# SCH_ORANGE-FCU_2022-09-27.net
KiCad netlist of a schematic drawn in EasyEDA
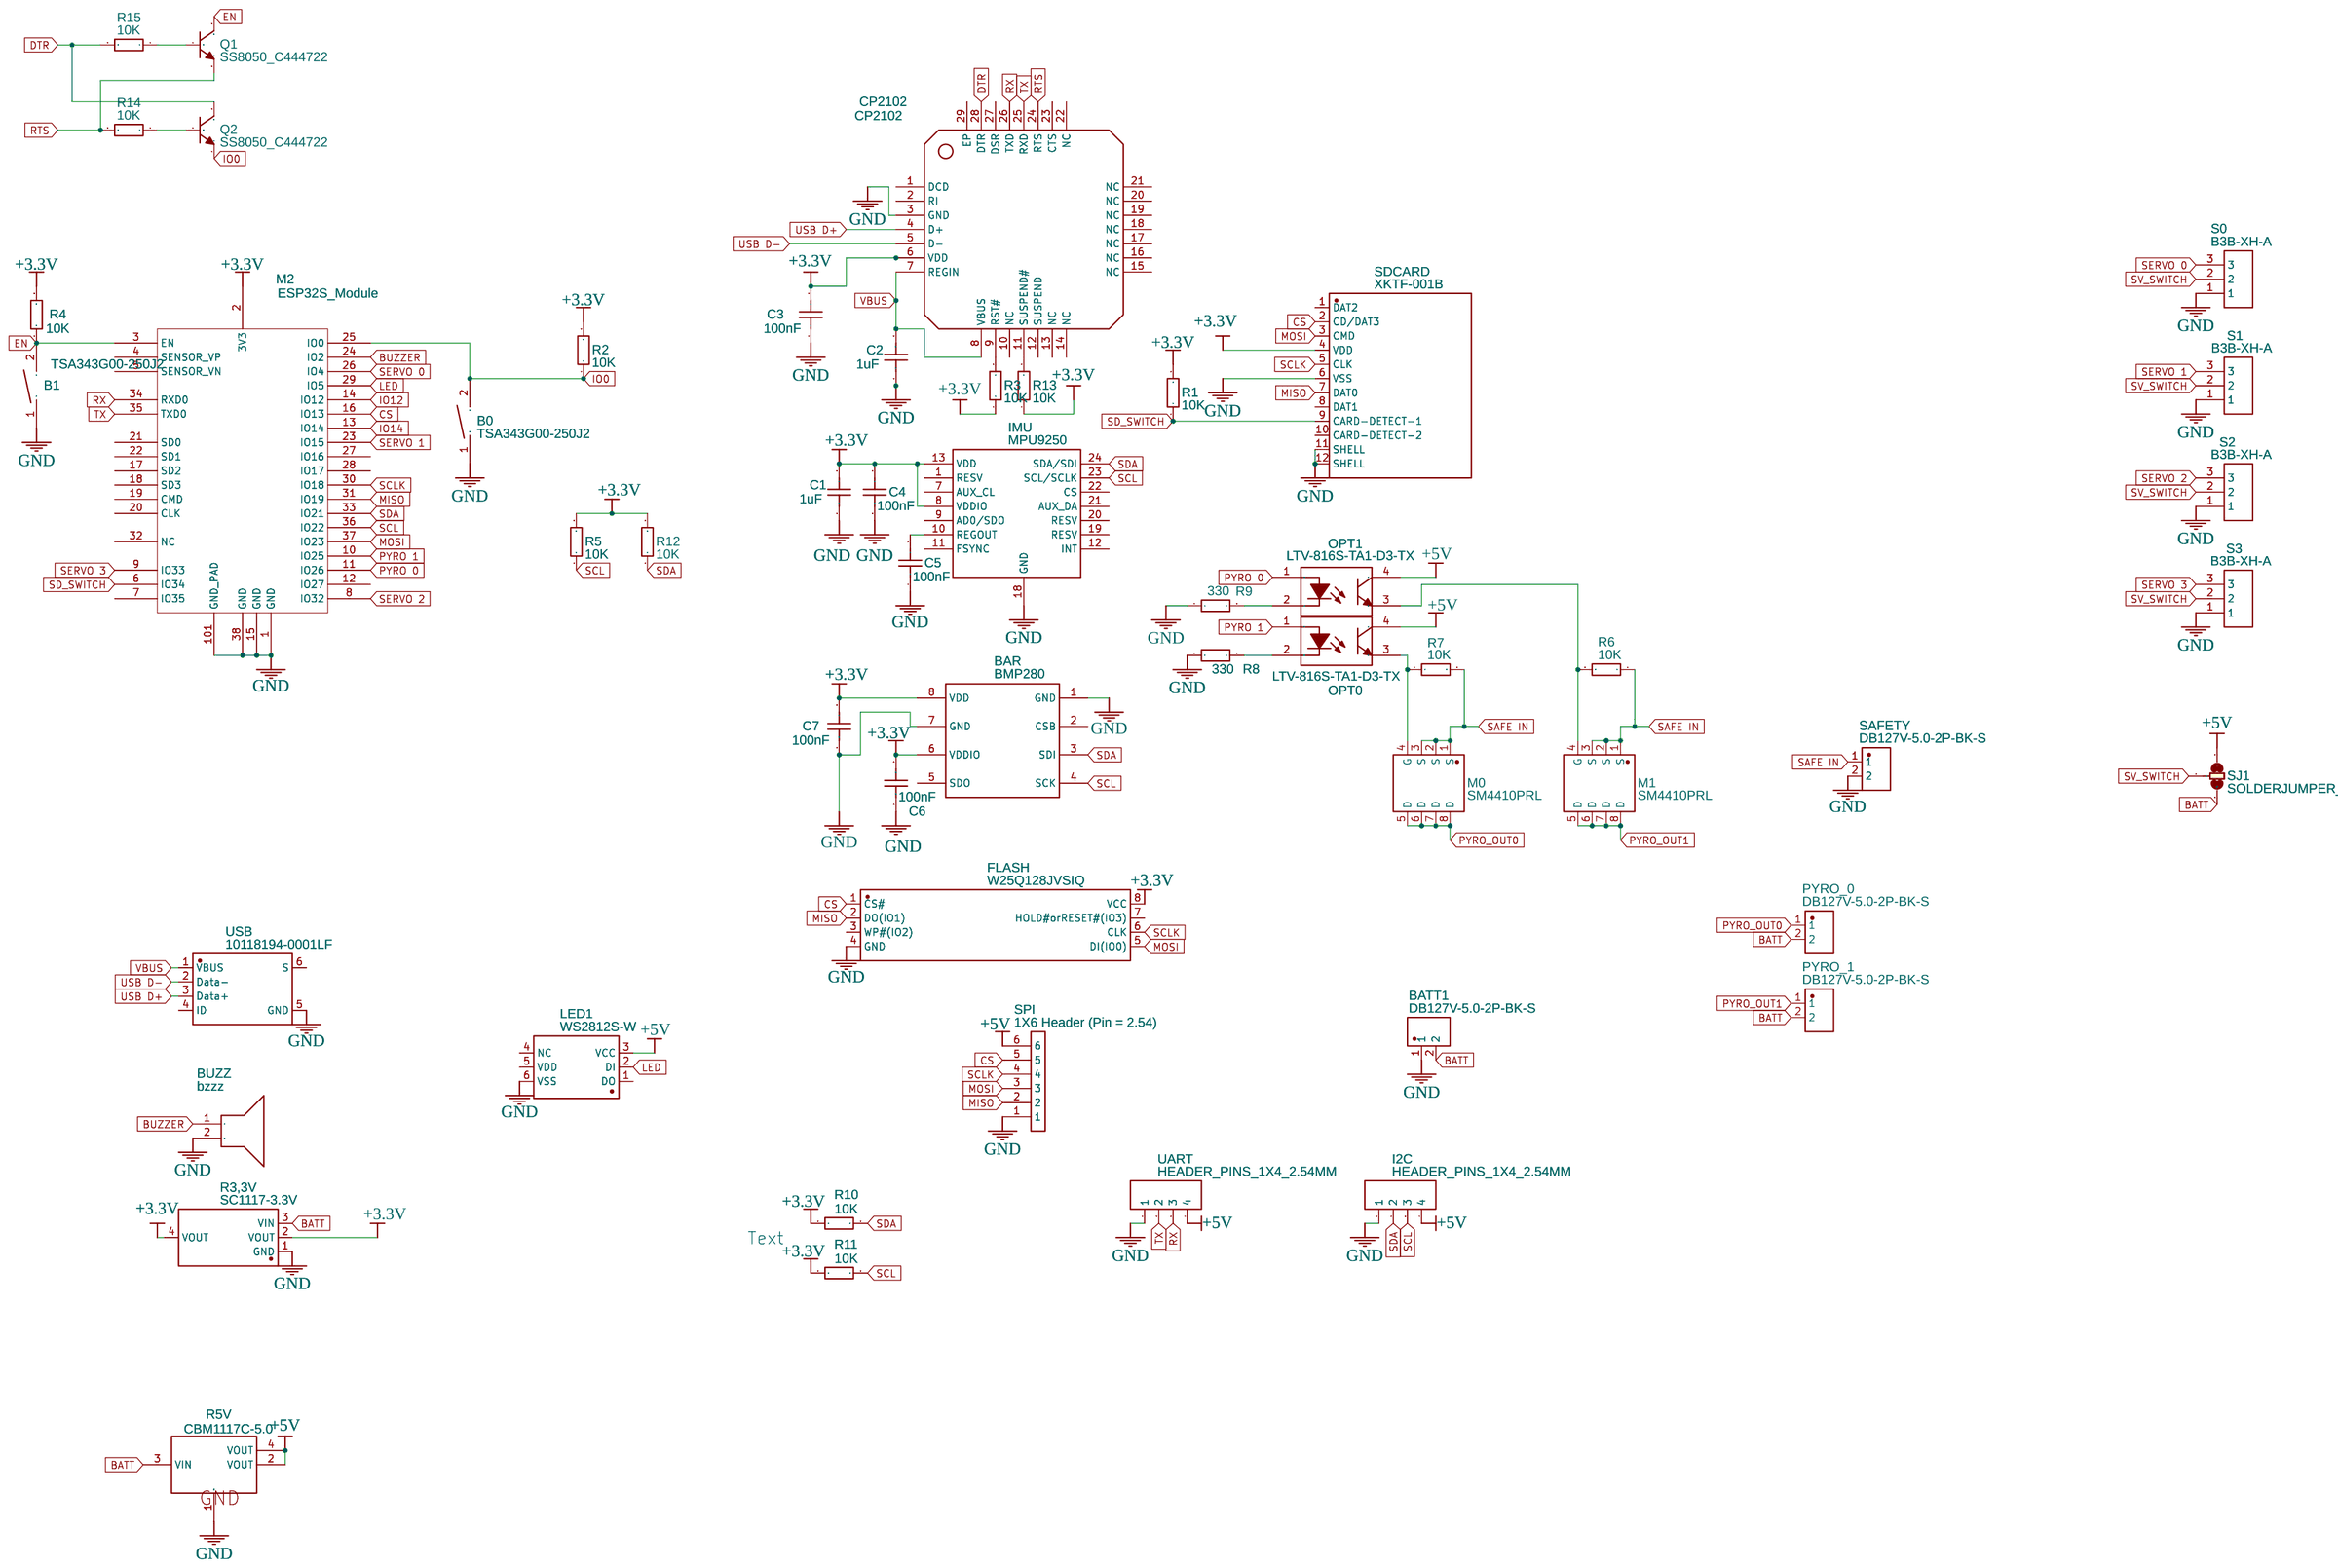
[diagram p0: schematic sheet]

(export (version "E")
  (design (tool "Eeschema 10.0.6"))
  (components
    (comp (ref "B0")
      (value "TSA343G00-250J2")
      (fields (field (name "BOM_Supplier Part") "C354946"))
      (libsource (lib "") (part "TSA343G00-250J2"))
    )
    (comp (ref "B1")
      (value "TSA343G00-250J2")
      (fields (field (name "BOM_Supplier Part") "C354946"))
      (libsource (lib "") (part "TSA343G00-250J2"))
    )
    (comp (ref "BAR")
      (value "BMP280")
      (fields (field (name "BOM_Supplier Part") "C83291"))
      (libsource (lib "") (part "BMP280"))
    )
    (comp (ref "BATT1")
      (value "DB127V-5.0-2P-BK-S")
      (fields (field (name "BOM_Supplier Part") "C430623"))
      (libsource (lib "") (part "DB127V-5.0-2P-BK-S_2"))
    )
    (comp (ref "BUZZ")
      (value "bzzz")
      (fields (field (name "BOM_Manufacturer Part") "FST-9018") (field (name "BOM_Supplier Part") "C391035"))
      (libsource (lib "") (part "FST-9018"))
    )
    (comp (ref "C1")
      (value "1uF")
      (fields
        (field (name "BOM_Manufacturer Part") "1206F105Z160CT")
        (field (name "BOM_Supplier Part") "C408911")
      )
      (libsource (lib "") (part "1206F105Z160CT"))
    )
    (comp (ref "C2")
      (value "1uF")
      (fields
        (field (name "BOM_Manufacturer Part") "1206F105Z160CT")
        (field (name "BOM_Supplier Part") "C408911")
      )
      (libsource (lib "") (part "1206F105Z160CT"))
    )
    (comp (ref "C3")
      (value "100nF")
      (fields
        (field (name "BOM_Manufacturer Part") "TCC1206X7R104K101DTS")
        (field (name "BOM_Supplier Part") "C696845")
      )
      (libsource (lib "") (part "TCC1206X7R104K101DTS"))
    )
    (comp (ref "C4")
      (value "100nF")
      (fields
        (field (name "BOM_Manufacturer Part") "TCC1206X7R104K101DTS")
        (field (name "BOM_Supplier Part") "C696845")
      )
      (libsource (lib "") (part "TCC1206X7R104K101DTS"))
    )
    (comp (ref "C5")
      (value "100nF")
      (fields
        (field (name "BOM_Manufacturer Part") "TCC1206X7R104K101DTS")
        (field (name "BOM_Supplier Part") "C696845")
      )
      (libsource (lib "") (part "TCC1206X7R104K101DTS"))
    )
    (comp (ref "C6")
      (value "100nF")
      (fields
        (field (name "BOM_Manufacturer Part") "TCC1206X7R104K101DTS")
        (field (name "BOM_Supplier Part") "C696845")
      )
      (libsource (lib "") (part "TCC1206X7R104K101DTS"))
    )
    (comp (ref "C7")
      (value "100nF")
      (fields
        (field (name "BOM_Manufacturer Part") "TCC1206X7R104K101DTS")
        (field (name "BOM_Supplier Part") "C696845")
      )
      (libsource (lib "") (part "TCC1206X7R104K101DTS"))
    )
    (comp (ref "CP2102")
      (value "CP2102")
      (fields (field (name "BOM_Manufacturer Part") "CP2102-GMR") (field (name "BOM_Supplier Part") "C6568"))
      (libsource (lib "") (part "CP2102-GMR"))
    )
    (comp (ref "FLASH")
      (value "W25Q128JVSIQ")
      (fields (field (name "BOM_Supplier Part") "C113767"))
      (libsource (lib "") (part "W25Q128JVSIQ"))
    )
    (comp (ref "I2C") (value "HEADER_PINS_1X4_2.54MM") (libsource (lib "") (part "HEADER_PINS_1X4_2.54MM")))
    (comp (ref "IMU") (value "MPU9250") (libsource (lib "") (part "MPU9250")))
    (comp (ref "LED1")
      (value "WS2812S-W")
      (fields (field (name "BOM_Supplier Part") "C114584"))
      (libsource (lib "") (part "WS2812S-W"))
    )
    (comp (ref "M0")
      (value "SM4410PRL")
      (fields (field (name "BOM_Supplier Part") "C235535"))
      (libsource (lib "") (part "SM4410PRL"))
    )
    (comp (ref "M1")
      (value "SM4410PRL")
      (fields (field (name "BOM_Supplier Part") "C235535"))
      (libsource (lib "") (part "SM4410PRL"))
    )
    (comp (ref "M2") (value "ESP32S_Module") (libsource (lib "") (part "ESP32S_Module")))
    (comp (ref "OPT0")
      (value "LTV-816S-TA1-D3-TX")
      (fields (field (name "BOM_Supplier Part") "C92647"))
      (libsource (lib "") (part "LTV-816S-TA1-D3-TX"))
    )
    (comp (ref "OPT1")
      (value "LTV-816S-TA1-D3-TX")
      (fields (field (name "BOM_Supplier Part") "C92647"))
      (libsource (lib "") (part "LTV-816S-TA1-D3-TX"))
    )
    (comp (ref "PYRO_0")
      (value "DB127V-5.0-2P-BK-S")
      (fields (field (name "BOM_Supplier Part") "C430623"))
      (libsource (lib "") (part "DB127V-5.0-2P-BK-S"))
    )
    (comp (ref "PYRO_1")
      (value "DB127V-5.0-2P-BK-S")
      (fields (field (name "BOM_Supplier Part") "C430623"))
      (libsource (lib "") (part "DB127V-5.0-2P-BK-S"))
    )
    (comp (ref "Q1")
      (value "SS8050_C444722")
      (fields (field (name "BOM_Manufacturer Part") "SS8050") (field (name "BOM_Supplier Part") "C444722"))
      (libsource (lib "") (part "SS8050_C444722"))
    )
    (comp (ref "Q2")
      (value "SS8050_C444722")
      (fields (field (name "BOM_Manufacturer Part") "SS8050") (field (name "BOM_Supplier Part") "C444722"))
      (libsource (lib "") (part "SS8050_C444722"))
    )
    (comp (ref "R1")
      (value "10K")
      (fields
        (field (name "BOM_Manufacturer Part") "AECR1206F10K0K9")
        (field (name "BOM_Supplier Part") "C328409")
      )
      (libsource (lib "") (part "AECR1206F10K0K9"))
    )
    (comp (ref "R2")
      (value "10K")
      (fields
        (field (name "BOM_Manufacturer Part") "AECR1206F10K0K9")
        (field (name "BOM_Supplier Part") "C328409")
      )
      (libsource (lib "") (part "AECR1206F10K0K9"))
    )
    (comp (ref "R3")
      (value "10K")
      (fields
        (field (name "BOM_Manufacturer Part") "AECR1206F10K0K9")
        (field (name "BOM_Supplier Part") "C328409")
      )
      (libsource (lib "") (part "AECR1206F10K0K9"))
    )
    (comp (ref "R3,3V")
      (value "SC1117-3.3V")
      (fields (field (name "BOM_Supplier Part") "C173386"))
      (libsource (lib "") (part "SC1117-3.3V"))
    )
    (comp (ref "R4")
      (value "10K")
      (fields
        (field (name "BOM_Manufacturer Part") "AECR1206F10K0K9")
        (field (name "BOM_Supplier Part") "C328409")
      )
      (libsource (lib "") (part "AECR1206F10K0K9"))
    )
    (comp (ref "R5")
      (value "10K")
      (fields
        (field (name "BOM_Manufacturer Part") "AECR1206F10K0K9")
        (field (name "BOM_Supplier Part") "C328409")
      )
      (libsource (lib "") (part "AECR1206F10K0K9"))
    )
    (comp (ref "R5V")
      (value "CBM1117C-5.0")
      (fields (field (name "BOM_Supplier Part") "C918918"))
      (libsource (lib "") (part "CBM1117C-5.0"))
    )
    (comp (ref "R6")
      (value "10K")
      (fields
        (field (name "BOM_Manufacturer Part") "AECR1206F10K0K9")
        (field (name "BOM_Supplier Part") "C328409")
      )
      (libsource (lib "") (part "AECR1206F10K0K9_2"))
    )
    (comp (ref "R7")
      (value "10K")
      (fields
        (field (name "BOM_Manufacturer Part") "AECR1206F10K0K9")
        (field (name "BOM_Supplier Part") "C328409")
      )
      (libsource (lib "") (part "AECR1206F10K0K9_1"))
    )
    (comp (ref "R8")
      (value "330")
      (fields
        (field (name "BOM_Manufacturer Part") "RTT06331JTP")
        (field (name "BOM_Supplier Part") "C104769")
      )
      (libsource (lib "") (part "RTT06331JTP"))
    )
    (comp (ref "R9")
      (value "330")
      (fields
        (field (name "BOM_Manufacturer Part") "RTT06331JTP")
        (field (name "BOM_Supplier Part") "C104769")
      )
      (libsource (lib "") (part "RTT06331JTP"))
    )
    (comp (ref "R10")
      (value "10K")
      (fields
        (field (name "BOM_Manufacturer Part") "AECR1206F10K0K9")
        (field (name "BOM_Supplier Part") "C328409")
      )
      (libsource (lib "") (part "AECR1206F10K0K9_1"))
    )
    (comp (ref "R11")
      (value "10K")
      (fields
        (field (name "BOM_Manufacturer Part") "AECR1206F10K0K9")
        (field (name "BOM_Supplier Part") "C328409")
      )
      (libsource (lib "") (part "AECR1206F10K0K9_1"))
    )
    (comp (ref "R12")
      (value "10K")
      (fields
        (field (name "BOM_Manufacturer Part") "AECR1206F10K0K9")
        (field (name "BOM_Supplier Part") "C328409")
      )
      (libsource (lib "") (part "AECR1206F10K0K9"))
    )
    (comp (ref "R13")
      (value "10K")
      (fields
        (field (name "BOM_Manufacturer Part") "AECR1206F10K0K9")
        (field (name "BOM_Supplier Part") "C328409")
      )
      (libsource (lib "") (part "AECR1206F10K0K9"))
    )
    (comp (ref "R14")
      (value "10K")
      (fields
        (field (name "BOM_Manufacturer Part") "AECR1206F10K0K9")
        (field (name "BOM_Supplier Part") "C328409")
      )
      (libsource (lib "") (part "AECR1206F10K0K9_2"))
    )
    (comp (ref "R15")
      (value "10K")
      (fields
        (field (name "BOM_Manufacturer Part") "AECR1206F10K0K9")
        (field (name "BOM_Supplier Part") "C328409")
      )
      (libsource (lib "") (part "AECR1206F10K0K9_2"))
    )
    (comp (ref "S0")
      (value "B3B-XH-A")
      (fields
        (field (name "BOM_Manufacturer Part") "B3B-XH-A(LF)(SN)")
        (field (name "BOM_Supplier Part") "C144394")
      )
      (libsource (lib "") (part "B3B-XH-A(LF)(SN)"))
    )
    (comp (ref "S1")
      (value "B3B-XH-A")
      (fields
        (field (name "BOM_Manufacturer Part") "B3B-XH-A(LF)(SN)")
        (field (name "BOM_Supplier Part") "C144394")
      )
      (libsource (lib "") (part "B3B-XH-A(LF)(SN)"))
    )
    (comp (ref "S2")
      (value "B3B-XH-A")
      (fields
        (field (name "BOM_Manufacturer Part") "B3B-XH-A(LF)(SN)")
        (field (name "BOM_Supplier Part") "C144394")
      )
      (libsource (lib "") (part "B3B-XH-A(LF)(SN)"))
    )
    (comp (ref "S3")
      (value "B3B-XH-A")
      (fields
        (field (name "BOM_Manufacturer Part") "B3B-XH-A(LF)(SN)")
        (field (name "BOM_Supplier Part") "C144394")
      )
      (libsource (lib "") (part "B3B-XH-A(LF)(SN)"))
    )
    (comp (ref "SAFETY")
      (value "DB127V-5.0-2P-BK-S")
      (fields (field (name "BOM_Supplier Part") "C430623"))
      (libsource (lib "") (part "DB127V-5.0-2P-BK-S_1"))
    )
    (comp (ref "SDCARD")
      (value "XKTF-001B")
      (fields (field (name "BOM_Supplier Part") "C381080"))
      (libsource (lib "") (part "XKTF-001B"))
    )
    (comp (ref "SJ1") (value "SOLDERJUMPER_2WAY-OLDS") (libsource (lib "") (part "SOLDERJUMPER_2WAY-OLDS")))
    (comp (ref "SPI")
      (value "1X6 Header (Pin = 2.54)")
      (fields (field (name "BOM_Manufacturer Part") "Male Header 2 pin"))
      (libsource (lib "") (part "1X6 Header (Pin = 2.54)"))
    )
    (comp (ref "UART")
      (value "HEADER_PINS_1X4_2.54MM")
      (libsource (lib "") (part "HEADER_PINS_1X4_2.54MM_1"))
    )
    (comp (ref "USB")
      (value "10118194-0001LF")
      (fields (field (name "BOM_Supplier Part") "C132563"))
      (libsource (lib "") (part "10118194-0001LF"))
    )
  )
  (nets
    (net (code "1") (name "+3.3V") (class "Default")
      (node (ref "BAR") (pin "6") (pinfunction "VDDIO_6") (pintype "unspecified"))
      (node (ref "BAR") (pin "8") (pinfunction "VDD_8") (pintype "unspecified"))
      (node (ref "C1") (pin "2") (pinfunction "2_2") (pintype "unspecified"))
      (node (ref "C3") (pin "2") (pinfunction "2_2") (pintype "unspecified"))
      (node (ref "C4") (pin "2") (pinfunction "2_2") (pintype "unspecified"))
      (node (ref "C6") (pin "2") (pinfunction "2_2") (pintype "unspecified"))
      (node (ref "C7") (pin "2") (pinfunction "2_2") (pintype "unspecified"))
      (node (ref "CP2102") (pin "6") (pinfunction "VDD_6") (pintype "unspecified"))
      (node (ref "FLASH") (pin "8") (pinfunction "VCC_8") (pintype "unspecified"))
      (node (ref "IMU") (pin "13") (pinfunction "VDD_13") (pintype "unspecified"))
      (node (ref "IMU") (pin "8") (pinfunction "VDDIO_8") (pintype "unspecified"))
      (node (ref "M2") (pin "2") (pinfunction "3V3_2") (pintype "passive"))
      (node (ref "R1") (pin "2") (pinfunction "2_2") (pintype "unspecified"))
      (node (ref "R10") (pin "1") (pinfunction "1_1") (pintype "unspecified"))
      (node (ref "R11") (pin "1") (pinfunction "1_1") (pintype "unspecified"))
      (node (ref "R12") (pin "2") (pinfunction "2_2") (pintype "unspecified"))
      (node (ref "R13") (pin "1") (pinfunction "1_1") (pintype "unspecified"))
      (node (ref "R2") (pin "2") (pinfunction "2_2") (pintype "unspecified"))
      (node (ref "R3") (pin "1") (pinfunction "1_1") (pintype "unspecified"))
      (node (ref "R3,3V") (pin "2") (pinfunction "VOUT_2") (pintype "unspecified"))
      (node (ref "R3,3V") (pin "4") (pinfunction "VOUT_4") (pintype "unspecified"))
      (node (ref "R4") (pin "2") (pinfunction "2_2") (pintype "unspecified"))
      (node (ref "R5") (pin "2") (pinfunction "2_2") (pintype "unspecified"))
      (node (ref "SDCARD") (pin "4") (pinfunction "VDD_4") (pintype "unspecified"))
    )
    (net (code "2") (name "+5V") (class "Default")
      (node (ref "I2C") (pin "4") (pinfunction "4_4") (pintype "unspecified"))
      (node (ref "LED1") (pin "3") (pinfunction "VCC_3") (pintype "unspecified"))
      (node (ref "OPT0") (pin "4") (pinfunction "4_4") (pintype "unspecified"))
      (node (ref "OPT1") (pin "4") (pinfunction "4_4") (pintype "unspecified"))
      (node (ref "R5V") (pin "2") (pinfunction "VOUT_2") (pintype "passive"))
      (node (ref "R5V") (pin "4") (pinfunction "VOUT_4") (pintype "passive"))
      (node (ref "SJ1") (pin "1") (pinfunction "1_1") (pintype "unspecified"))
      (node (ref "SPI") (pin "6") (pinfunction "6_6") (pintype "unspecified"))
      (node (ref "UART") (pin "4") (pinfunction "4_4") (pintype "unspecified"))
    )
    (net (code "3") (name "BATT") (class "Default")
      (node (ref "BATT1") (pin "2") (pinfunction "2_2") (pintype "unspecified"))
      (node (ref "PYRO_0") (pin "2") (pinfunction "2_2") (pintype "unspecified"))
      (node (ref "PYRO_1") (pin "2") (pinfunction "2_2") (pintype "unspecified"))
      (node (ref "R3,3V") (pin "3") (pinfunction "VIN_3") (pintype "unspecified"))
      (node (ref "R5V") (pin "3") (pinfunction "VIN_3") (pintype "passive"))
      (node (ref "SJ1") (pin "3") (pinfunction "3_3") (pintype "unspecified"))
    )
    (net (code "4") (name "BUZZER") (class "Default")
      (node (ref "BUZZ") (pin "1") (pinfunction "1_1") (pintype "unspecified"))
      (node (ref "M2") (pin "24") (pinfunction "IO2_24") (pintype "unspecified"))
    )
    (net (code "5") (name "CS") (class "Default")
      (node (ref "FLASH") (pin "1") (pinfunction "CS#_1") (pintype "unspecified"))
      (node (ref "M2") (pin "16") (pinfunction "IO13_16") (pintype "unspecified"))
      (node (ref "SDCARD") (pin "2") (pinfunction "CD/DAT3_2") (pintype "unspecified"))
      (node (ref "SPI") (pin "5") (pinfunction "5_5") (pintype "unspecified"))
    )
    (net (code "6") (name "DTR") (class "Default")
      (node (ref "CP2102") (pin "28") (pinfunction "DTR_28") (pintype "unspecified"))
      (node (ref "Q2") (pin "3") (pinfunction "C_3") (pintype "unspecified"))
      (node (ref "R15") (pin "2") (pinfunction "2_2") (pintype "unspecified"))
    )
    (net (code "7") (name "EN") (class "Default")
      (node (ref "B1") (pin "2") (pinfunction "2_2") (pintype "input"))
      (node (ref "M2") (pin "3") (pinfunction "EN_3") (pintype "passive"))
      (node (ref "Q1") (pin "3") (pinfunction "C_3") (pintype "unspecified"))
      (node (ref "R4") (pin "1") (pinfunction "1_1") (pintype "unspecified"))
    )
    (net (code "8") (name "GND") (class "Default")
      (node (ref "B0") (pin "1") (pinfunction "1_1") (pintype "input"))
      (node (ref "B1") (pin "1") (pinfunction "1_1") (pintype "input"))
      (node (ref "BAR") (pin "1") (pinfunction "GND_1") (pintype "unspecified"))
      (node (ref "BAR") (pin "7") (pinfunction "GND_7") (pintype "unspecified"))
      (node (ref "BATT1") (pin "1") (pinfunction "1_1") (pintype "unspecified"))
      (node (ref "BUZZ") (pin "2") (pinfunction "2_2") (pintype "unspecified"))
      (node (ref "C1") (pin "1") (pinfunction "1_1") (pintype "unspecified"))
      (node (ref "C2") (pin "1") (pinfunction "1_1") (pintype "unspecified"))
      (node (ref "C3") (pin "1") (pinfunction "1_1") (pintype "unspecified"))
      (node (ref "C4") (pin "1") (pinfunction "1_1") (pintype "unspecified"))
      (node (ref "C5") (pin "1") (pinfunction "1_1") (pintype "unspecified"))
      (node (ref "C6") (pin "1") (pinfunction "1_1") (pintype "unspecified"))
      (node (ref "C7") (pin "1") (pinfunction "1_1") (pintype "unspecified"))
      (node (ref "CP2102") (pin "3") (pinfunction "GND_3") (pintype "unspecified"))
      (node (ref "FLASH") (pin "4") (pinfunction "GND_4") (pintype "unspecified"))
      (node (ref "I2C") (pin "1") (pinfunction "1_1") (pintype "unspecified"))
      (node (ref "IMU") (pin "18") (pinfunction "GND_18") (pintype "unspecified"))
      (node (ref "LED1") (pin "6") (pinfunction "VSS_6") (pintype "unspecified"))
      (node (ref "M2") (pin "1") (pinfunction "GND_1") (pintype "passive"))
      (node (ref "M2") (pin "101") (pinfunction "GND_PAD_101") (pintype "passive"))
      (node (ref "M2") (pin "15") (pinfunction "GND_15") (pintype "passive"))
      (node (ref "M2") (pin "38") (pinfunction "GND_38") (pintype "passive"))
      (node (ref "R3,3V") (pin "1") (pinfunction "GND_1") (pintype "unspecified"))
      (node (ref "R5V") (pin "1") (pinfunction "GND_1") (pintype "passive"))
      (node (ref "R8") (pin "1") (pinfunction "1_1") (pintype "input"))
      (node (ref "R9") (pin "1") (pinfunction "1_1") (pintype "input"))
      (node (ref "S0") (pin "1") (pinfunction "1_1") (pintype "unspecified"))
      (node (ref "S1") (pin "1") (pinfunction "1_1") (pintype "unspecified"))
      (node (ref "S2") (pin "1") (pinfunction "1_1") (pintype "unspecified"))
      (node (ref "S3") (pin "1") (pinfunction "1_1") (pintype "unspecified"))
      (node (ref "SAFETY") (pin "2") (pinfunction "2_2") (pintype "unspecified"))
      (node (ref "SDCARD") (pin "11") (pinfunction "SHELL_11") (pintype "unspecified"))
      (node (ref "SDCARD") (pin "12") (pinfunction "SHELL_12") (pintype "unspecified"))
      (node (ref "SDCARD") (pin "6") (pinfunction "VSS_6") (pintype "unspecified"))
      (node (ref "SPI") (pin "1") (pinfunction "1_1") (pintype "unspecified"))
      (node (ref "UART") (pin "1") (pinfunction "1_1") (pintype "unspecified"))
      (node (ref "USB") (pin "5") (pinfunction "GND_5") (pintype "unspecified"))
    )
    (net (code "9") (name "IO0") (class "Default")
      (node (ref "B0") (pin "2") (pinfunction "2_2") (pintype "input"))
      (node (ref "M2") (pin "25") (pinfunction "IO0_25") (pintype "unspecified"))
      (node (ref "Q2") (pin "2") (pinfunction "E_2") (pintype "unspecified"))
      (node (ref "R2") (pin "1") (pinfunction "1_1") (pintype "unspecified"))
    )
    (net (code "10") (name "IO12") (class "Default")
      (node (ref "M2") (pin "14") (pinfunction "IO12_14") (pintype "unspecified"))
    )
    (net (code "11") (name "IO14") (class "Default")
      (node (ref "M2") (pin "13") (pinfunction "IO14_13") (pintype "unspecified"))
    )
    (net (code "12") (name "LED") (class "Default")
      (node (ref "LED1") (pin "2") (pinfunction "DI_2") (pintype "unspecified"))
      (node (ref "M2") (pin "29") (pinfunction "IO5_29") (pintype "unspecified"))
    )
    (net (code "13") (name "MISO") (class "Default")
      (node (ref "FLASH") (pin "2") (pinfunction "DO(IO1)_2") (pintype "unspecified"))
      (node (ref "M2") (pin "31") (pinfunction "IO19_31") (pintype "unspecified"))
      (node (ref "SDCARD") (pin "7") (pinfunction "DAT0_7") (pintype "unspecified"))
      (node (ref "SPI") (pin "2") (pinfunction "2_2") (pintype "unspecified"))
    )
    (net (code "14") (name "MOSI") (class "Default")
      (node (ref "FLASH") (pin "5") (pinfunction "DI(IO0)_5") (pintype "unspecified"))
      (node (ref "M2") (pin "37") (pinfunction "IO23_37") (pintype "unspecified"))
      (node (ref "SDCARD") (pin "3") (pinfunction "CMD_3") (pintype "unspecified"))
      (node (ref "SPI") (pin "3") (pinfunction "3_3") (pintype "unspecified"))
    )
    (net (code "15") (name "Net-(CP2102-RST#)") (class "Default")
      (node (ref "CP2102") (pin "9") (pinfunction "RST#_9") (pintype "unspecified"))
      (node (ref "R3") (pin "2") (pinfunction "2_2") (pintype "unspecified"))
    )
    (net (code "16") (name "Net-(CP2102-SUSPEND#)") (class "Default")
      (node (ref "CP2102") (pin "11") (pinfunction "SUSPEND#_11") (pintype "unspecified"))
      (node (ref "R13") (pin "2") (pinfunction "2_2") (pintype "unspecified"))
    )
    (net (code "17") (name "Net-(IMU-REGOUT)") (class "Default")
      (node (ref "C5") (pin "2") (pinfunction "2_2") (pintype "unspecified"))
      (node (ref "IMU") (pin "10") (pinfunction "REGOUT_10") (pintype "unspecified"))
    )
    (net (code "18") (name "Net-(M0-G)") (class "Default")
      (node (ref "M0") (pin "4") (pinfunction "G_4") (pintype "unspecified"))
      (node (ref "OPT0") (pin "3") (pinfunction "3_3") (pintype "unspecified"))
      (node (ref "R7") (pin "1") (pinfunction "1_1") (pintype "unspecified"))
    )
    (net (code "19") (name "Net-(M1-G)") (class "Default")
      (node (ref "M1") (pin "4") (pinfunction "G_4") (pintype "unspecified"))
      (node (ref "OPT1") (pin "3") (pinfunction "3_3") (pintype "unspecified"))
      (node (ref "R6") (pin "2") (pinfunction "2_2") (pintype "unspecified"))
    )
    (net (code "20") (name "Net-(OPT0-Pad2)") (class "Default")
      (node (ref "OPT0") (pin "2") (pinfunction "2_2") (pintype "unspecified"))
      (node (ref "R8") (pin "2") (pinfunction "2_2") (pintype "input"))
    )
    (net (code "21") (name "Net-(OPT1-Pad2)") (class "Default")
      (node (ref "OPT1") (pin "2") (pinfunction "2_2") (pintype "unspecified"))
      (node (ref "R9") (pin "2") (pinfunction "2_2") (pintype "input"))
    )
    (net (code "22") (name "Net-(Q1-B)") (class "Default")
      (node (ref "Q1") (pin "1") (pinfunction "B_1") (pintype "unspecified"))
      (node (ref "R15") (pin "1") (pinfunction "1_1") (pintype "unspecified"))
    )
    (net (code "23") (name "Net-(Q2-B)") (class "Default")
      (node (ref "Q2") (pin "1") (pinfunction "B_1") (pintype "unspecified"))
      (node (ref "R14") (pin "1") (pinfunction "1_1") (pintype "unspecified"))
    )
    (net (code "24") (name "PYRO 0") (class "Default")
      (node (ref "M2") (pin "11") (pinfunction "IO26_11") (pintype "unspecified"))
      (node (ref "OPT1") (pin "1") (pinfunction "1_1") (pintype "unspecified"))
    )
    (net (code "25") (name "PYRO 1") (class "Default")
      (node (ref "M2") (pin "10") (pinfunction "IO25_10") (pintype "unspecified"))
      (node (ref "OPT0") (pin "1") (pinfunction "1_1") (pintype "unspecified"))
    )
    (net (code "26") (name "PYRO_OUT0") (class "Default")
      (node (ref "M0") (pin "5") (pinfunction "D_5") (pintype "unspecified"))
      (node (ref "M0") (pin "6") (pinfunction "D_6") (pintype "unspecified"))
      (node (ref "M0") (pin "7") (pinfunction "D_7") (pintype "unspecified"))
      (node (ref "M0") (pin "8") (pinfunction "D_8") (pintype "unspecified"))
      (node (ref "PYRO_0") (pin "1") (pinfunction "1_1") (pintype "unspecified"))
    )
    (net (code "27") (name "PYRO_OUT1") (class "Default")
      (node (ref "M1") (pin "5") (pinfunction "D_5") (pintype "unspecified"))
      (node (ref "M1") (pin "6") (pinfunction "D_6") (pintype "unspecified"))
      (node (ref "M1") (pin "7") (pinfunction "D_7") (pintype "unspecified"))
      (node (ref "M1") (pin "8") (pinfunction "D_8") (pintype "unspecified"))
      (node (ref "PYRO_1") (pin "1") (pinfunction "1_1") (pintype "unspecified"))
    )
    (net (code "28") (name "RTS") (class "Default")
      (node (ref "CP2102") (pin "24") (pinfunction "RTS_24") (pintype "unspecified"))
      (node (ref "Q1") (pin "2") (pinfunction "E_2") (pintype "unspecified"))
      (node (ref "R14") (pin "2") (pinfunction "2_2") (pintype "unspecified"))
    )
    (net (code "29") (name "RX") (class "Default")
      (node (ref "CP2102") (pin "26") (pinfunction "TXD_26") (pintype "unspecified"))
      (node (ref "M2") (pin "34") (pinfunction "RXD0_34") (pintype "unspecified"))
      (node (ref "UART") (pin "3") (pinfunction "3_3") (pintype "unspecified"))
    )
    (net (code "30") (name "SAFE IN") (class "Default")
      (node (ref "M0") (pin "1") (pinfunction "S_1") (pintype "unspecified"))
      (node (ref "M0") (pin "2") (pinfunction "S_2") (pintype "unspecified"))
      (node (ref "M0") (pin "3") (pinfunction "S_3") (pintype "unspecified"))
      (node (ref "M1") (pin "1") (pinfunction "S_1") (pintype "unspecified"))
      (node (ref "M1") (pin "2") (pinfunction "S_2") (pintype "unspecified"))
      (node (ref "M1") (pin "3") (pinfunction "S_3") (pintype "unspecified"))
      (node (ref "R6") (pin "1") (pinfunction "1_1") (pintype "unspecified"))
      (node (ref "R7") (pin "2") (pinfunction "2_2") (pintype "unspecified"))
      (node (ref "SAFETY") (pin "1") (pinfunction "1_1") (pintype "unspecified"))
    )
    (net (code "31") (name "SCL") (class "Default")
      (node (ref "BAR") (pin "4") (pinfunction "SCK_4") (pintype "unspecified"))
      (node (ref "I2C") (pin "3") (pinfunction "3_3") (pintype "unspecified"))
      (node (ref "IMU") (pin "23") (pinfunction "SCL/SCLK_23") (pintype "unspecified"))
      (node (ref "M2") (pin "36") (pinfunction "IO22_36") (pintype "unspecified"))
      (node (ref "R11") (pin "2") (pinfunction "2_2") (pintype "unspecified"))
      (node (ref "R5") (pin "1") (pinfunction "1_1") (pintype "unspecified"))
    )
    (net (code "32") (name "SCLK") (class "Default")
      (node (ref "FLASH") (pin "6") (pinfunction "CLK_6") (pintype "unspecified"))
      (node (ref "M2") (pin "30") (pinfunction "IO18_30") (pintype "unspecified"))
      (node (ref "SDCARD") (pin "5") (pinfunction "CLK_5") (pintype "unspecified"))
      (node (ref "SPI") (pin "4") (pinfunction "4_4") (pintype "unspecified"))
    )
    (net (code "33") (name "SDA") (class "Default")
      (node (ref "BAR") (pin "3") (pinfunction "SDI_3") (pintype "unspecified"))
      (node (ref "I2C") (pin "2") (pinfunction "2_2") (pintype "unspecified"))
      (node (ref "IMU") (pin "24") (pinfunction "SDA/SDI_24") (pintype "unspecified"))
      (node (ref "M2") (pin "33") (pinfunction "IO21_33") (pintype "unspecified"))
      (node (ref "R10") (pin "2") (pinfunction "2_2") (pintype "unspecified"))
      (node (ref "R12") (pin "1") (pinfunction "1_1") (pintype "unspecified"))
    )
    (net (code "34") (name "SD_SWITCH") (class "Default")
      (node (ref "M2") (pin "6") (pinfunction "IO34_6") (pintype "unspecified"))
      (node (ref "R1") (pin "1") (pinfunction "1_1") (pintype "unspecified"))
      (node (ref "SDCARD") (pin "9") (pinfunction "CARD-DETECT-1_9") (pintype "unspecified"))
    )
    (net (code "35") (name "SERVO 0") (class "Default")
      (node (ref "M2") (pin "26") (pinfunction "IO4_26") (pintype "unspecified"))
      (node (ref "S0") (pin "3") (pinfunction "3_3") (pintype "unspecified"))
    )
    (net (code "36") (name "SERVO 1") (class "Default")
      (node (ref "M2") (pin "23") (pinfunction "IO15_23") (pintype "unspecified"))
      (node (ref "S1") (pin "3") (pinfunction "3_3") (pintype "unspecified"))
    )
    (net (code "37") (name "SERVO 2") (class "Default")
      (node (ref "M2") (pin "8") (pinfunction "IO32_8") (pintype "unspecified"))
      (node (ref "S2") (pin "3") (pinfunction "3_3") (pintype "unspecified"))
    )
    (net (code "38") (name "SERVO 3") (class "Default")
      (node (ref "M2") (pin "9") (pinfunction "IO33_9") (pintype "unspecified"))
      (node (ref "S3") (pin "3") (pinfunction "3_3") (pintype "unspecified"))
    )
    (net (code "39") (name "SV_SWITCH") (class "Default")
      (node (ref "S0") (pin "2") (pinfunction "2_2") (pintype "unspecified"))
      (node (ref "S1") (pin "2") (pinfunction "2_2") (pintype "unspecified"))
      (node (ref "S2") (pin "2") (pinfunction "2_2") (pintype "unspecified"))
      (node (ref "S3") (pin "2") (pinfunction "2_2") (pintype "unspecified"))
      (node (ref "SJ1") (pin "2") (pinfunction "2_2") (pintype "unspecified"))
    )
    (net (code "40") (name "TX") (class "Default")
      (node (ref "CP2102") (pin "25") (pinfunction "RXD_25") (pintype "unspecified"))
      (node (ref "M2") (pin "35") (pinfunction "TXD0_35") (pintype "unspecified"))
      (node (ref "UART") (pin "2") (pinfunction "2_2") (pintype "unspecified"))
    )
    (net (code "41") (name "USB D+") (class "Default")
      (node (ref "CP2102") (pin "4") (pinfunction "D+_4") (pintype "unspecified"))
      (node (ref "USB") (pin "3") (pinfunction "Data+_3") (pintype "unspecified"))
    )
    (net (code "42") (name "USB D-") (class "Default")
      (node (ref "CP2102") (pin "5") (pinfunction "D-_5") (pintype "unspecified"))
      (node (ref "USB") (pin "2") (pinfunction "Data-_2") (pintype "unspecified"))
    )
    (net (code "43") (name "VBUS") (class "Default")
      (node (ref "C2") (pin "2") (pinfunction "2_2") (pintype "unspecified"))
      (node (ref "CP2102") (pin "7") (pinfunction "REGIN_7") (pintype "unspecified"))
      (node (ref "CP2102") (pin "8") (pinfunction "VBUS_8") (pintype "unspecified"))
      (node (ref "USB") (pin "1") (pinfunction "VBUS_1") (pintype "unspecified"))
    )
    (net (code "44") (name "unconnected-(BAR-CSB-Pad2)") (class "Default")
      (node (ref "BAR") (pin "2") (pinfunction "CSB_2") (pintype "unspecified"))
    )
    (net (code "45") (name "unconnected-(BAR-SDO-Pad5)") (class "Default")
      (node (ref "BAR") (pin "5") (pinfunction "SDO_5") (pintype "unspecified"))
    )
    (net (code "46") (name "unconnected-(CP2102-CTS-Pad23)") (class "Default")
      (node (ref "CP2102") (pin "23") (pinfunction "CTS_23") (pintype "unspecified"))
    )
    (net (code "47") (name "unconnected-(CP2102-DCD-Pad1)") (class "Default")
      (node (ref "CP2102") (pin "1") (pinfunction "DCD_1") (pintype "unspecified"))
    )
    (net (code "48") (name "unconnected-(CP2102-DSR-Pad27)") (class "Default")
      (node (ref "CP2102") (pin "27") (pinfunction "DSR_27") (pintype "unspecified"))
    )
    (net (code "49") (name "unconnected-(CP2102-EP-Pad29)") (class "Default")
      (node (ref "CP2102") (pin "29") (pinfunction "EP_29") (pintype "unspecified"))
    )
    (net (code "50") (name "unconnected-(CP2102-NC-Pad10)") (class "Default")
      (node (ref "CP2102") (pin "10") (pinfunction "NC_10") (pintype "unspecified"))
    )
    (net (code "51") (name "unconnected-(CP2102-NC-Pad13)") (class "Default")
      (node (ref "CP2102") (pin "13") (pinfunction "NC_13") (pintype "unspecified"))
    )
    (net (code "52") (name "unconnected-(CP2102-NC-Pad14)") (class "Default")
      (node (ref "CP2102") (pin "14") (pinfunction "NC_14") (pintype "unspecified"))
    )
    (net (code "53") (name "unconnected-(CP2102-NC-Pad15)") (class "Default")
      (node (ref "CP2102") (pin "15") (pinfunction "NC_15") (pintype "unspecified"))
    )
    (net (code "54") (name "unconnected-(CP2102-NC-Pad16)") (class "Default")
      (node (ref "CP2102") (pin "16") (pinfunction "NC_16") (pintype "unspecified"))
    )
    (net (code "55") (name "unconnected-(CP2102-NC-Pad17)") (class "Default")
      (node (ref "CP2102") (pin "17") (pinfunction "NC_17") (pintype "unspecified"))
    )
    (net (code "56") (name "unconnected-(CP2102-NC-Pad18)") (class "Default")
      (node (ref "CP2102") (pin "18") (pinfunction "NC_18") (pintype "unspecified"))
    )
    (net (code "57") (name "unconnected-(CP2102-NC-Pad19)") (class "Default")
      (node (ref "CP2102") (pin "19") (pinfunction "NC_19") (pintype "unspecified"))
    )
    (net (code "58") (name "unconnected-(CP2102-NC-Pad20)") (class "Default")
      (node (ref "CP2102") (pin "20") (pinfunction "NC_20") (pintype "unspecified"))
    )
    (net (code "59") (name "unconnected-(CP2102-NC-Pad21)") (class "Default")
      (node (ref "CP2102") (pin "21") (pinfunction "NC_21") (pintype "unspecified"))
    )
    (net (code "60") (name "unconnected-(CP2102-NC-Pad22)") (class "Default")
      (node (ref "CP2102") (pin "22") (pinfunction "NC_22") (pintype "unspecified"))
    )
    (net (code "61") (name "unconnected-(CP2102-RI-Pad2)") (class "Default")
      (node (ref "CP2102") (pin "2") (pinfunction "RI_2") (pintype "unspecified"))
    )
    (net (code "62") (name "unconnected-(CP2102-SUSPEND-Pad12)") (class "Default")
      (node (ref "CP2102") (pin "12") (pinfunction "SUSPEND_12") (pintype "unspecified"))
    )
    (net (code "63") (name "unconnected-(FLASH-HOLD#orRESET#(IO3)-Pad7)") (class "Default")
      (node (ref "FLASH") (pin "7") (pinfunction "HOLD#orRESET#(IO3)_7") (pintype "unspecified"))
    )
    (net (code "64") (name "unconnected-(FLASH-WP#(IO2)-Pad3)") (class "Default")
      (node (ref "FLASH") (pin "3") (pinfunction "WP#(IO2)_3") (pintype "unspecified"))
    )
    (net (code "65") (name "unconnected-(IMU-AD0{slash}SDO-Pad9)") (class "Default")
      (node (ref "IMU") (pin "9") (pinfunction "AD0/SDO_9") (pintype "unspecified"))
    )
    (net (code "66") (name "unconnected-(IMU-AUX_CL-Pad7)") (class "Default")
      (node (ref "IMU") (pin "7") (pinfunction "AUX_CL_7") (pintype "unspecified"))
    )
    (net (code "67") (name "unconnected-(IMU-AUX_DA-Pad21)") (class "Default")
      (node (ref "IMU") (pin "21") (pinfunction "AUX_DA_21") (pintype "unspecified"))
    )
    (net (code "68") (name "unconnected-(IMU-CS-Pad22)") (class "Default")
      (node (ref "IMU") (pin "22") (pinfunction "CS_22") (pintype "unspecified"))
    )
    (net (code "69") (name "unconnected-(IMU-FSYNC-Pad11)") (class "Default")
      (node (ref "IMU") (pin "11") (pinfunction "FSYNC_11") (pintype "unspecified"))
    )
    (net (code "70") (name "unconnected-(IMU-INT-Pad12)") (class "Default")
      (node (ref "IMU") (pin "12") (pinfunction "INT_12") (pintype "unspecified"))
    )
    (net (code "71") (name "unconnected-(IMU-RESV-Pad1)") (class "Default")
      (node (ref "IMU") (pin "1") (pinfunction "RESV_1") (pintype "unspecified"))
    )
    (net (code "72") (name "unconnected-(IMU-RESV-Pad19)") (class "Default")
      (node (ref "IMU") (pin "19") (pinfunction "RESV_19") (pintype "unspecified"))
    )
    (net (code "73") (name "unconnected-(IMU-RESV-Pad20)") (class "Default")
      (node (ref "IMU") (pin "20") (pinfunction "RESV_20") (pintype "unspecified"))
    )
    (net (code "74") (name "unconnected-(LED1-DO-Pad1)") (class "Default")
      (node (ref "LED1") (pin "1") (pinfunction "DO_1") (pintype "unspecified"))
    )
    (net (code "75") (name "unconnected-(LED1-NC-Pad4)") (class "Default")
      (node (ref "LED1") (pin "4") (pinfunction "NC_4") (pintype "unspecified"))
    )
    (net (code "76") (name "unconnected-(LED1-VDD-Pad5)") (class "Default")
      (node (ref "LED1") (pin "5") (pinfunction "VDD_5") (pintype "unspecified"))
    )
    (net (code "77") (name "unconnected-(M2-CLK-Pad20)") (class "Default")
      (node (ref "M2") (pin "20") (pinfunction "CLK_20") (pintype "unspecified"))
    )
    (net (code "78") (name "unconnected-(M2-CMD-Pad19)") (class "Default")
      (node (ref "M2") (pin "19") (pinfunction "CMD_19") (pintype "unspecified"))
    )
    (net (code "79") (name "unconnected-(M2-IO16-Pad27)") (class "Default")
      (node (ref "M2") (pin "27") (pinfunction "IO16_27") (pintype "unspecified"))
    )
    (net (code "80") (name "unconnected-(M2-IO17-Pad28)") (class "Default")
      (node (ref "M2") (pin "28") (pinfunction "IO17_28") (pintype "unspecified"))
    )
    (net (code "81") (name "unconnected-(M2-IO27-Pad12)") (class "Default")
      (node (ref "M2") (pin "12") (pinfunction "IO27_12") (pintype "unspecified"))
    )
    (net (code "82") (name "unconnected-(M2-IO35-Pad7)") (class "Default")
      (node (ref "M2") (pin "7") (pinfunction "IO35_7") (pintype "unspecified"))
    )
    (net (code "83") (name "unconnected-(M2-NC-Pad32)") (class "Default")
      (node (ref "M2") (pin "32") (pinfunction "NC_32") (pintype "unspecified"))
    )
    (net (code "84") (name "unconnected-(M2-SD0-Pad21)") (class "Default")
      (node (ref "M2") (pin "21") (pinfunction "SD0_21") (pintype "unspecified"))
    )
    (net (code "85") (name "unconnected-(M2-SD1-Pad22)") (class "Default")
      (node (ref "M2") (pin "22") (pinfunction "SD1_22") (pintype "unspecified"))
    )
    (net (code "86") (name "unconnected-(M2-SD2-Pad17)") (class "Default")
      (node (ref "M2") (pin "17") (pinfunction "SD2_17") (pintype "unspecified"))
    )
    (net (code "87") (name "unconnected-(M2-SD3-Pad18)") (class "Default")
      (node (ref "M2") (pin "18") (pinfunction "SD3_18") (pintype "unspecified"))
    )
    (net (code "88") (name "unconnected-(M2-SENSOR_VN-Pad5)") (class "Default")
      (node (ref "M2") (pin "5") (pinfunction "SENSOR_VN_5") (pintype "unspecified"))
    )
    (net (code "89") (name "unconnected-(M2-SENSOR_VP-Pad4)") (class "Default")
      (node (ref "M2") (pin "4") (pinfunction "SENSOR_VP_4") (pintype "unspecified"))
    )
    (net (code "90") (name "unconnected-(SDCARD-CARD-DETECT-2-Pad10)") (class "Default")
      (node (ref "SDCARD") (pin "10") (pinfunction "CARD-DETECT-2_10") (pintype "unspecified"))
    )
    (net (code "91") (name "unconnected-(SDCARD-DAT1-Pad8)") (class "Default")
      (node (ref "SDCARD") (pin "8") (pinfunction "DAT1_8") (pintype "unspecified"))
    )
    (net (code "92") (name "unconnected-(SDCARD-DAT2-Pad1)") (class "Default")
      (node (ref "SDCARD") (pin "1") (pinfunction "DAT2_1") (pintype "unspecified"))
    )
    (net (code "93") (name "unconnected-(USB-ID-Pad4)") (class "Default")
      (node (ref "USB") (pin "4") (pinfunction "ID_4") (pintype "unspecified"))
    )
    (net (code "94") (name "unconnected-(USB-S-Pad6)") (class "Default")
      (node (ref "USB") (pin "6") (pinfunction "S_6") (pintype "unspecified"))
    )
  )
)
